# design.net
KiCad netlist of a schematic drawn in Altium Designer
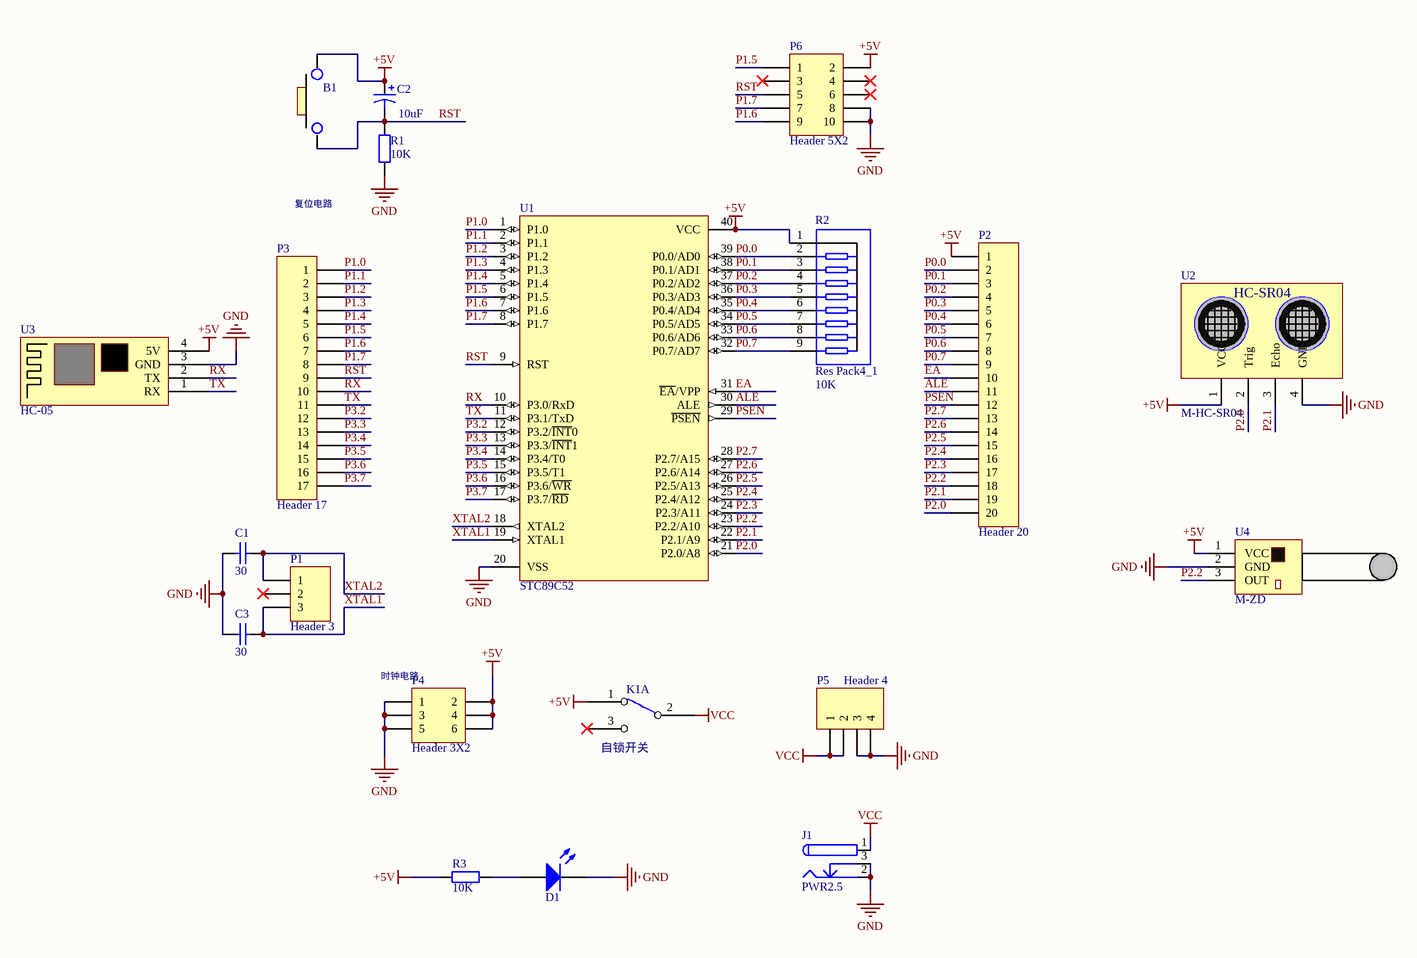
[diagram p0: 婴儿监测系统.SchDoc]

(export (version "E")
  (design (tool "Eeschema 10.0.6"))
  (components
    (comp (ref "B1") (value "Button") (footprint "BUTTON") (libsource (lib "51 lib") (part "Button")))
    (comp (ref "C1")
      (value "30")
      (footprint "C-RAD")
      (description "无极性电容")
      (fields (field (name "Comment") "Cap") (field (name "PUBLISHER") "Altium Limited"))
      (libsource (lib "51 lib") (part "Cap"))
    )
    (comp (ref "C2")
      (value "10uF")
      (footprint "C-RB-5.0")
      (description "有极性插件电容")
      (libsource (lib "Interim") (part "Cap Pol2"))
    )
    (comp (ref "C3")
      (value "30")
      (footprint "C-RAD")
      (description "无极性电容")
      (fields (field (name "Comment") "Cap") (field (name "PUBLISHER") "Altium Limited"))
      (libsource (lib "51 lib") (part "Cap"))
    )
    (comp (ref "D1")
      (value "LED0")
      (footprint "LED_A2")
      (description "发光二极管")
      (fields (field (name "PUBLISHER") "Altium Limited"))
      (libsource (lib "51 lib") (part "LED0"))
    )
    (comp (ref "J1")
      (value "PWR2.5")
      (footprint "kld-DC(2.5)")
      (description "Low Voltage Power Supply Connector")
      (fields (field (name "PUBLISHER") "Altium Limited"))
      (libsource (lib "Miscellaneous Connectors") (part "PWR2.5"))
    )
    (comp (ref "K1")
      (value "自锁开关")
      (footprint "SW-TH_6PIN-L5.80-W5.80-BL")
      (description "双档拨动开关")
      (libsource (lib "Switch") (part "双档拨动开关"))
    )
    (comp (ref "P1")
      (value "Header 3")
      (footprint "HDR1X3")
      (description "Header, 3-Pin")
      (fields (field (name "PUBLISHER") "Altium Limited"))
      (libsource (lib "Miscellaneous Connectors") (part "Header 3"))
    )
    (comp (ref "P2")
      (value "Header 20")
      (footprint "HDR1X20")
      (description "Header, 20-Pin")
      (fields (field (name "PUBLISHER") "Altium Limited"))
      (libsource (lib "Miscellaneous Connectors") (part "Header 20"))
    )
    (comp (ref "P3")
      (value "Header 17")
      (footprint "HDR1X17")
      (description "Header, 17-Pin")
      (fields (field (name "PUBLISHER") "Altium Limited"))
      (libsource (lib "Miscellaneous Connectors") (part "Header 17"))
    )
    (comp (ref "P4")
      (value "Header 3X2")
      (footprint "HDR2X3")
      (description "Header, 3-Pin, Dual row")
      (fields (field (name "PUBLISHER") "Altium Limited"))
      (libsource (lib "Miscellaneous Connectors") (part "Header 3X2"))
    )
    (comp (ref "P5")
      (value "Header 4")
      (footprint "HDR1X4")
      (description "Header, 4-Pin")
      (fields (field (name "PUBLISHER") "Altium Limited"))
      (libsource (lib "Miscellaneous Connectors") (part "Header 4"))
    )
    (comp (ref "P6")
      (value "Header 5X2")
      (footprint "HDR2X5")
      (description "Header, 5-Pin, Dual row")
      (fields (field (name "PUBLISHER") "Altium Limited"))
      (libsource (lib "Miscellaneous Connectors") (part "Header 5X2"))
    )
    (comp (ref "R1")
      (value "10K")
      (footprint "AXIAL-0.3")
      (description "贴片电阻")
      (fields (field (name "Comment") "Res1") (field (name "PUBLISHER") "Altium Limited"))
      (libsource (lib "51 lib") (part "Res1"))
    )
    (comp (ref "R2")
      (value "Res Pack4_1")
      (footprint "HDR1X9")
      (description "Isolated Resistor Network")
      (fields (field (name "ALTIUM_VALUE") "10K") (field (name "PUBLISHER") "Altium Limited"))
      (libsource (lib "51 lib") (part "Res Pack4_1"))
    )
    (comp (ref "R3")
      (value "10K")
      (footprint "AXIAL-0.3")
      (description "贴片电阻")
      (fields (field (name "Comment") "Res1") (field (name "PUBLISHER") "Altium Limited"))
      (libsource (lib "") (part "Res1_1"))
    )
    (comp (ref "U1")
      (value "STC89C52")
      (footprint "DIP-40 (fan)")
      (description "51系列单片机")
      (fields (field (name "PUBLISHER") "Altium Limited"))
      (libsource (lib "51 lib") (part "STC89C52"))
    )
    (comp (ref "U2")
      (value "M-HC-SR04")
      (footprint "M-HC-SR04")
      (description "超声波模块")
      (libsource (lib "51 lib") (part "M-HC-SR04"))
    )
    (comp (ref "U3")
      (value "HC-05")
      (footprint "HC-04")
      (description "蓝牙模块")
      (libsource (lib "51 lib") (part "HC-05"))
    )
    (comp (ref "U4")
      (value "M-ZD")
      (footprint "M-ZD")
      (description "MIC声音模块")
      (libsource (lib "51 lib") (part "M-zhendong"))
    )
  )
  (nets
    (net (code "1") (name "+5V") (class "Default")
      (node (ref "B1") (pin "2") (pinfunction "2_2") (pintype "passive"))
      (node (ref "C2") (pin "1") (pinfunction "1_1") (pintype "passive"))
      (node (ref "K1") (pin "1") (pinfunction "1_1") (pintype "passive"))
      (node (ref "P2") (pin "1") (pinfunction "1_1") (pintype "passive"))
      (node (ref "P4") (pin "2") (pinfunction "2_2") (pintype "passive"))
      (node (ref "P4") (pin "4") (pinfunction "4_4") (pintype "passive"))
      (node (ref "P4") (pin "6") (pinfunction "6_6") (pintype "passive"))
      (node (ref "P6") (pin "2") (pinfunction "2_2") (pintype "passive"))
      (node (ref "R2") (pin "1") (pinfunction "1_1") (pintype "passive"))
      (node (ref "R3") (pin "1") (pinfunction "1_1") (pintype "passive"))
      (node (ref "U1") (pin "40") (pinfunction "VCC_40") (pintype "power_in"))
      (node (ref "U2") (pin "1") (pinfunction "VCC_1") (pintype "passive"))
      (node (ref "U3") (pin "4") (pinfunction "5V_4") (pintype "passive"))
      (node (ref "U4") (pin "1") (pinfunction "VCC_1") (pintype "passive"))
    )
    (net (code "2") (name "/ALE") (class "Default")
      (node (ref "P2") (pin "11") (pinfunction "11_11") (pintype "passive"))
      (node (ref "U1") (pin "30") (pinfunction "ALE_30") (pintype "output"))
    )
    (net (code "3") (name "/EA") (class "Default")
      (node (ref "P2") (pin "10") (pinfunction "10_10") (pintype "passive"))
      (node (ref "U1") (pin "31") (pinfunction "~{EA}/VPP_31") (pintype "input"))
    )
    (net (code "4") (name "/P0.0") (class "Default")
      (node (ref "P2") (pin "2") (pinfunction "2_2") (pintype "passive"))
      (node (ref "R2") (pin "2") (pinfunction "2_2") (pintype "passive"))
      (node (ref "U1") (pin "39") (pinfunction "P0.0/AD0_39") (pintype "bidirectional"))
    )
    (net (code "5") (name "/P0.1") (class "Default")
      (node (ref "P2") (pin "3") (pinfunction "3_3") (pintype "passive"))
      (node (ref "R2") (pin "3") (pinfunction "3_3") (pintype "passive"))
      (node (ref "U1") (pin "38") (pinfunction "P0.1/AD1_38") (pintype "bidirectional"))
    )
    (net (code "6") (name "/P0.2") (class "Default")
      (node (ref "P2") (pin "4") (pinfunction "4_4") (pintype "passive"))
      (node (ref "R2") (pin "4") (pinfunction "4_4") (pintype "passive"))
      (node (ref "U1") (pin "37") (pinfunction "P0.2/AD2_37") (pintype "bidirectional"))
    )
    (net (code "7") (name "/P0.3") (class "Default")
      (node (ref "P2") (pin "5") (pinfunction "5_5") (pintype "passive"))
      (node (ref "R2") (pin "5") (pinfunction "5_5") (pintype "passive"))
      (node (ref "U1") (pin "36") (pinfunction "P0.3/AD3_36") (pintype "bidirectional"))
    )
    (net (code "8") (name "/P0.4") (class "Default")
      (node (ref "P2") (pin "6") (pinfunction "6_6") (pintype "passive"))
      (node (ref "R2") (pin "6") (pinfunction "6_6") (pintype "passive"))
      (node (ref "U1") (pin "35") (pinfunction "P0.4/AD4_35") (pintype "bidirectional"))
    )
    (net (code "9") (name "/P0.5") (class "Default")
      (node (ref "P2") (pin "7") (pinfunction "7_7") (pintype "passive"))
      (node (ref "R2") (pin "7") (pinfunction "7_7") (pintype "passive"))
      (node (ref "U1") (pin "34") (pinfunction "P0.5/AD5_34") (pintype "bidirectional"))
    )
    (net (code "10") (name "/P0.6") (class "Default")
      (node (ref "P2") (pin "8") (pinfunction "8_8") (pintype "passive"))
      (node (ref "R2") (pin "8") (pinfunction "8_8") (pintype "passive"))
      (node (ref "U1") (pin "33") (pinfunction "P0.6/AD6_33") (pintype "bidirectional"))
    )
    (net (code "11") (name "/P0.7") (class "Default")
      (node (ref "P2") (pin "9") (pinfunction "9_9") (pintype "passive"))
      (node (ref "R2") (pin "9") (pinfunction "9_9") (pintype "passive"))
      (node (ref "U1") (pin "32") (pinfunction "P0.7/AD7_32") (pintype "bidirectional"))
    )
    (net (code "12") (name "/P1.0") (class "Default")
      (node (ref "P3") (pin "1") (pinfunction "1_1") (pintype "passive"))
      (node (ref "U1") (pin "1") (pinfunction "P1.0_1") (pintype "bidirectional"))
    )
    (net (code "13") (name "/P1.1") (class "Default")
      (node (ref "P3") (pin "2") (pinfunction "2_2") (pintype "passive"))
      (node (ref "U1") (pin "2") (pinfunction "P1.1_2") (pintype "bidirectional"))
    )
    (net (code "14") (name "/P1.2") (class "Default")
      (node (ref "P3") (pin "3") (pinfunction "3_3") (pintype "passive"))
      (node (ref "U1") (pin "3") (pinfunction "P1.2_3") (pintype "bidirectional"))
    )
    (net (code "15") (name "/P1.3") (class "Default")
      (node (ref "P3") (pin "4") (pinfunction "4_4") (pintype "passive"))
      (node (ref "U1") (pin "4") (pinfunction "P1.3_4") (pintype "bidirectional"))
    )
    (net (code "16") (name "/P1.4") (class "Default")
      (node (ref "P3") (pin "5") (pinfunction "5_5") (pintype "passive"))
      (node (ref "U1") (pin "5") (pinfunction "P1.4_5") (pintype "bidirectional"))
    )
    (net (code "17") (name "/P1.5") (class "Default")
      (node (ref "P3") (pin "6") (pinfunction "6_6") (pintype "passive"))
      (node (ref "P6") (pin "1") (pinfunction "1_1") (pintype "passive"))
      (node (ref "U1") (pin "6") (pinfunction "P1.5_6") (pintype "bidirectional"))
    )
    (net (code "18") (name "/P1.6") (class "Default")
      (node (ref "P3") (pin "7") (pinfunction "7_7") (pintype "passive"))
      (node (ref "P6") (pin "9") (pinfunction "9_9") (pintype "passive"))
      (node (ref "U1") (pin "7") (pinfunction "P1.6_7") (pintype "bidirectional"))
    )
    (net (code "19") (name "/P1.7") (class "Default")
      (node (ref "P3") (pin "8") (pinfunction "8_8") (pintype "passive"))
      (node (ref "P6") (pin "7") (pinfunction "7_7") (pintype "passive"))
      (node (ref "U1") (pin "8") (pinfunction "P1.7_8") (pintype "bidirectional"))
    )
    (net (code "20") (name "/P2.0") (class "Default")
      (node (ref "P2") (pin "20") (pinfunction "20_20") (pintype "passive"))
      (node (ref "U1") (pin "21") (pinfunction "P2.0/A8_21") (pintype "bidirectional"))
      (node (ref "U2") (pin "2") (pinfunction "Trig_2") (pintype "passive"))
    )
    (net (code "21") (name "/P2.1") (class "Default")
      (node (ref "P2") (pin "19") (pinfunction "19_19") (pintype "passive"))
      (node (ref "U1") (pin "22") (pinfunction "P2.1/A9_22") (pintype "bidirectional"))
      (node (ref "U2") (pin "3") (pinfunction "Echo_3") (pintype "passive"))
    )
    (net (code "22") (name "/P2.2") (class "Default")
      (node (ref "P2") (pin "18") (pinfunction "18_18") (pintype "passive"))
      (node (ref "U1") (pin "23") (pinfunction "P2.2/A10_23") (pintype "bidirectional"))
      (node (ref "U4") (pin "3") (pinfunction "OUT_3") (pintype "passive"))
    )
    (net (code "23") (name "/P2.3") (class "Default")
      (node (ref "P2") (pin "17") (pinfunction "17_17") (pintype "passive"))
      (node (ref "U1") (pin "24") (pinfunction "P2.3/A11_24") (pintype "bidirectional"))
    )
    (net (code "24") (name "/P2.4") (class "Default")
      (node (ref "P2") (pin "16") (pinfunction "16_16") (pintype "passive"))
      (node (ref "U1") (pin "25") (pinfunction "P2.4/A12_25") (pintype "bidirectional"))
    )
    (net (code "25") (name "/P2.5") (class "Default")
      (node (ref "P2") (pin "15") (pinfunction "15_15") (pintype "passive"))
      (node (ref "U1") (pin "26") (pinfunction "P2.5/A13_26") (pintype "bidirectional"))
    )
    (net (code "26") (name "/P2.6") (class "Default")
      (node (ref "P2") (pin "14") (pinfunction "14_14") (pintype "passive"))
      (node (ref "U1") (pin "27") (pinfunction "P2.6/A14_27") (pintype "bidirectional"))
    )
    (net (code "27") (name "/P2.7") (class "Default")
      (node (ref "P2") (pin "13") (pinfunction "13_13") (pintype "passive"))
      (node (ref "U1") (pin "28") (pinfunction "P2.7/A15_28") (pintype "bidirectional"))
    )
    (net (code "28") (name "/P3.2") (class "Default")
      (node (ref "P3") (pin "12") (pinfunction "12_12") (pintype "passive"))
      (node (ref "U1") (pin "12") (pinfunction "P3.2/~{INT}0_12") (pintype "bidirectional"))
    )
    (net (code "29") (name "/P3.3") (class "Default")
      (node (ref "P3") (pin "13") (pinfunction "13_13") (pintype "passive"))
      (node (ref "U1") (pin "13") (pinfunction "P3.3/~{INT}1_13") (pintype "bidirectional"))
    )
    (net (code "30") (name "/P3.4") (class "Default")
      (node (ref "P3") (pin "14") (pinfunction "14_14") (pintype "passive"))
      (node (ref "U1") (pin "14") (pinfunction "P3.4/T0_14") (pintype "bidirectional"))
    )
    (net (code "31") (name "/P3.5") (class "Default")
      (node (ref "P3") (pin "15") (pinfunction "15_15") (pintype "passive"))
      (node (ref "U1") (pin "15") (pinfunction "P3.5/T1_15") (pintype "bidirectional"))
    )
    (net (code "32") (name "/P3.6") (class "Default")
      (node (ref "P3") (pin "16") (pinfunction "16_16") (pintype "passive"))
      (node (ref "U1") (pin "16") (pinfunction "P3.6/~{WR}_16") (pintype "bidirectional"))
    )
    (net (code "33") (name "/P3.7") (class "Default")
      (node (ref "P3") (pin "17") (pinfunction "17_17") (pintype "passive"))
      (node (ref "U1") (pin "17") (pinfunction "P3.7/~{RD}_17") (pintype "bidirectional"))
    )
    (net (code "34") (name "/PSEN") (class "Default")
      (node (ref "P2") (pin "12") (pinfunction "12_12") (pintype "passive"))
      (node (ref "U1") (pin "29") (pinfunction "~{PSEN}_29") (pintype "output"))
    )
    (net (code "35") (name "/RST") (class "Default")
      (node (ref "B1") (pin "1") (pinfunction "1_1") (pintype "passive"))
      (node (ref "C2") (pin "2") (pinfunction "2_2") (pintype "passive"))
      (node (ref "P3") (pin "9") (pinfunction "9_9") (pintype "passive"))
      (node (ref "P6") (pin "5") (pinfunction "5_5") (pintype "passive"))
      (node (ref "R1") (pin "2") (pinfunction "2_2") (pintype "passive"))
      (node (ref "U1") (pin "9") (pinfunction "RST_9") (pintype "input"))
    )
    (net (code "36") (name "/RX") (class "Default")
      (node (ref "P3") (pin "10") (pinfunction "10_10") (pintype "passive"))
      (node (ref "U1") (pin "10") (pinfunction "P3.0/RxD_10") (pintype "bidirectional"))
      (node (ref "U3") (pin "2") (pinfunction "TX_2") (pintype "passive"))
    )
    (net (code "37") (name "/TX") (class "Default")
      (node (ref "P3") (pin "11") (pinfunction "11_11") (pintype "passive"))
      (node (ref "U1") (pin "11") (pinfunction "P3.1/TxD_11") (pintype "bidirectional"))
      (node (ref "U3") (pin "1") (pinfunction "RX_1") (pintype "passive"))
    )
    (net (code "38") (name "/XTAL1") (class "Default")
      (node (ref "C3") (pin "2") (pinfunction "2_2") (pintype "passive"))
      (node (ref "P1") (pin "3") (pinfunction "3_3") (pintype "passive"))
      (node (ref "U1") (pin "19") (pinfunction "XTAL1_19") (pintype "input"))
    )
    (net (code "39") (name "/XTAL2") (class "Default")
      (node (ref "C1") (pin "2") (pinfunction "2_2") (pintype "passive"))
      (node (ref "P1") (pin "1") (pinfunction "1_1") (pintype "passive"))
      (node (ref "U1") (pin "18") (pinfunction "XTAL2_18") (pintype "output"))
    )
    (net (code "40") (name "GND") (class "Default")
      (node (ref "C1") (pin "1") (pinfunction "1_1") (pintype "passive"))
      (node (ref "C3") (pin "1") (pinfunction "1_1") (pintype "passive"))
      (node (ref "D1") (pin "2") (pinfunction "K_2") (pintype "passive"))
      (node (ref "J1") (pin "2") (pinfunction "2_2") (pintype "power_in"))
      (node (ref "J1") (pin "3") (pinfunction "3_3") (pintype "power_in"))
      (node (ref "P4") (pin "1") (pinfunction "1_1") (pintype "passive"))
      (node (ref "P4") (pin "3") (pinfunction "3_3") (pintype "passive"))
      (node (ref "P4") (pin "5") (pinfunction "5_5") (pintype "passive"))
      (node (ref "P5") (pin "3") (pinfunction "3_3") (pintype "passive"))
      (node (ref "P5") (pin "4") (pinfunction "4_4") (pintype "passive"))
      (node (ref "P6") (pin "10") (pinfunction "10_10") (pintype "passive"))
      (node (ref "P6") (pin "8") (pinfunction "8_8") (pintype "passive"))
      (node (ref "R1") (pin "1") (pinfunction "1_1") (pintype "passive"))
      (node (ref "U1") (pin "20") (pinfunction "VSS_20") (pintype "power_in"))
      (node (ref "U2") (pin "4") (pinfunction "GND_4") (pintype "passive"))
      (node (ref "U3") (pin "3") (pinfunction "GND_3") (pintype "passive"))
      (node (ref "U4") (pin "2") (pinfunction "GND_2") (pintype "passive"))
    )
    (net (code "41") (name "Net-(D1-A)") (class "Default")
      (node (ref "D1") (pin "1") (pinfunction "A_1") (pintype "passive"))
      (node (ref "R3") (pin "2") (pinfunction "2_2") (pintype "passive"))
    )
    (net (code "42") (name "VCC") (class "Default")
      (node (ref "J1") (pin "1") (pinfunction "1_1") (pintype "power_in"))
      (node (ref "K1") (pin "2") (pinfunction "2_2") (pintype "passive"))
      (node (ref "P5") (pin "1") (pinfunction "1_1") (pintype "passive"))
      (node (ref "P5") (pin "2") (pinfunction "2_2") (pintype "passive"))
    )
    (net (code "43") (name "unconnected-(K1-Pad3)") (class "Default")
      (node (ref "K1") (pin "3") (pinfunction "3_3") (pintype "passive+no_connect"))
    )
    (net (code "44") (name "unconnected-(P1-Pad2)") (class "Default")
      (node (ref "P1") (pin "2") (pinfunction "2_2") (pintype "passive+no_connect"))
    )
    (net (code "45") (name "unconnected-(P6-Pad3)") (class "Default")
      (node (ref "P6") (pin "3") (pinfunction "3_3") (pintype "passive+no_connect"))
    )
    (net (code "46") (name "unconnected-(P6-Pad4)") (class "Default")
      (node (ref "P6") (pin "4") (pinfunction "4_4") (pintype "passive+no_connect"))
    )
    (net (code "47") (name "unconnected-(P6-Pad6)") (class "Default")
      (node (ref "P6") (pin "6") (pinfunction "6_6") (pintype "passive+no_connect"))
    )
  )
)
